# HVPS_SMD-eagle.net
KiCad netlist of a schematic drawn in EAGLE
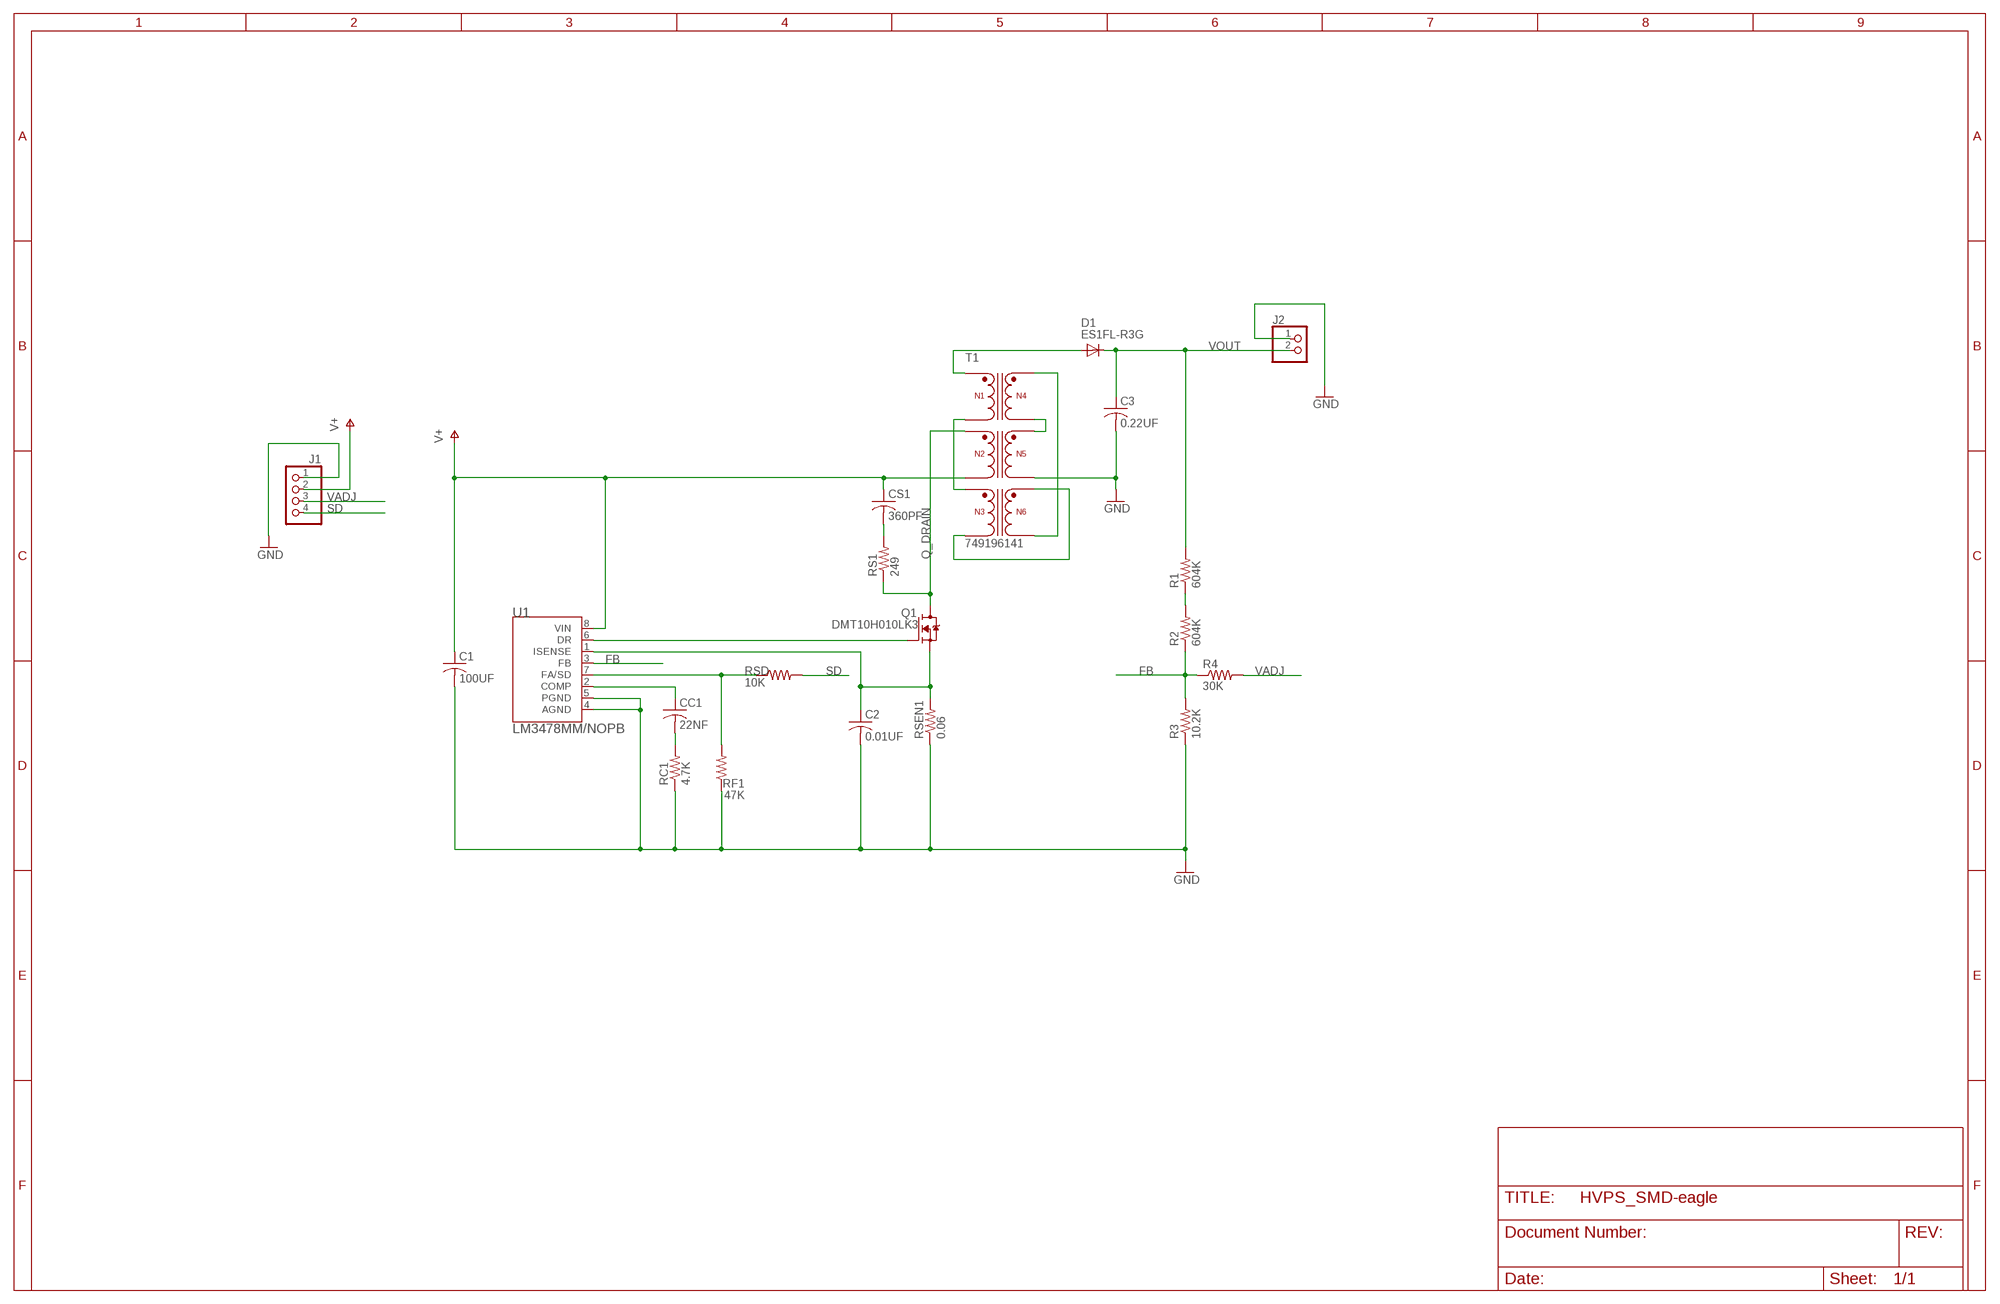
[diagram p0: schematic, sheet 1]

(export (version "E")
  (design (tool "Eeschema 10.0.6"))
  (components
    (comp (ref "C1")
      (value "100UF")
      (footprint "eagle-import:C1210")
      (libsource (lib "eagle-import") (part "C-USC1210"))
    )
    (comp (ref "C2")
      (value "0.01UF")
      (footprint "eagle-import:C0603")
      (libsource (lib "eagle-import") (part "C-USC0603"))
    )
    (comp (ref "C3")
      (value "0.22UF")
      (footprint "eagle-import:C1210")
      (libsource (lib "eagle-import") (part "C-USC1210"))
    )
    (comp (ref "CC1")
      (value "22NF")
      (footprint "eagle-import:C0603")
      (libsource (lib "eagle-import") (part "C-USC0603"))
    )
    (comp (ref "CS1")
      (value "360PF")
      (footprint "eagle-import:C0603")
      (libsource (lib "eagle-import") (part "C-USC0603"))
    )
    (comp (ref "D1")
      (value "ES1FL-R3G")
      (footprint "eagle-import:SMA")
      (libsource (lib "eagle-import") (part "ES1FL-R3G"))
    )
    (comp (ref "J1")
      (value "PINHD-1X4")
      (footprint "eagle-import:1X04")
      (libsource (lib "eagle-import") (part "PINHD-1X4"))
    )
    (comp (ref "J2")
      (value "PINHD-1X2")
      (footprint "eagle-import:1X02")
      (libsource (lib "eagle-import") (part "PINHD-1X2"))
    )
    (comp (ref "Q1")
      (value "DMT10H010LK3")
      (footprint "eagle-import:TO252")
      (libsource (lib "eagle-import") (part "DMT10H010LK3"))
    )
    (comp (ref "R1")
      (value "604K")
      (footprint "eagle-import:R0805")
      (libsource (lib "eagle-import") (part "R-US_R0805"))
    )
    (comp (ref "R2")
      (value "604K")
      (footprint "eagle-import:R0805")
      (libsource (lib "eagle-import") (part "R-US_R0805"))
    )
    (comp (ref "R3")
      (value "10.2K")
      (footprint "eagle-import:R0603")
      (libsource (lib "eagle-import") (part "R-US_R0603"))
    )
    (comp (ref "R4")
      (value "30K")
      (footprint "eagle-import:R0603")
      (libsource (lib "eagle-import") (part "R-US_R0603"))
    )
    (comp (ref "RC1")
      (value "4.7K")
      (footprint "eagle-import:R0805")
      (libsource (lib "eagle-import") (part "R-US_R0805"))
    )
    (comp (ref "RF1")
      (value "47K")
      (footprint "eagle-import:R0603")
      (libsource (lib "eagle-import") (part "R-US_R0603"))
    )
    (comp (ref "RS1")
      (value "249")
      (footprint "eagle-import:R1206")
      (libsource (lib "eagle-import") (part "R-US_R1206"))
    )
    (comp (ref "RSD")
      (value "10K")
      (footprint "eagle-import:R0603")
      (libsource (lib "eagle-import") (part "R-US_R0603"))
    )
    (comp (ref "RSEN1")
      (value "0.06")
      (footprint "eagle-import:R2010")
      (libsource (lib "eagle-import") (part "R-US_R2010"))
    )
    (comp (ref "T1")
      (value "749196141")
      (footprint "eagle-import:749196141")
      (libsource (lib "eagle-import") (part "749196141"))
    )
    (comp (ref "U1")
      (value "LM3478MM/NOPB")
      (footprint "eagle-import:MUA08A")
      (fields (field (name "MANUFACTURER_PART_NUMBER") "LM3478MMNOPB"))
      (libsource (lib "eagle-import") (part "LM3478MM/NOPB"))
    )
  )
  (nets
    (net (code "1") (name "/FB") (class "Default")
      (node (ref "R2") (pin "1") (pinfunction "1_1") (pintype "passive"))
      (node (ref "R3") (pin "2") (pinfunction "2_2") (pintype "passive"))
      (node (ref "R4") (pin "1") (pinfunction "1_1") (pintype "passive"))
      (node (ref "U1") (pin "3") (pinfunction "FB_3") (pintype "passive"))
    )
    (net (code "2") (name "/Q_DRAIN") (class "Default")
      (node (ref "Q1") (pin "3") (pinfunction "D_3") (pintype "passive"))
      (node (ref "RS1") (pin "1") (pinfunction "1_1") (pintype "passive"))
      (node (ref "T1") (pin "2") (pinfunction "N2_2") (pintype "passive"))
    )
    (net (code "3") (name "/SD") (class "Default")
      (node (ref "J1") (pin "4") (pinfunction "4_4") (pintype "passive"))
      (node (ref "RSD") (pin "2") (pinfunction "2_2") (pintype "passive"))
    )
    (net (code "4") (name "/VADJ") (class "Default")
      (node (ref "J1") (pin "3") (pinfunction "3_3") (pintype "passive"))
      (node (ref "R4") (pin "2") (pinfunction "2_2") (pintype "passive"))
    )
    (net (code "5") (name "/VOUT") (class "Default")
      (node (ref "C3") (pin "1") (pinfunction "1_1") (pintype "passive"))
      (node (ref "D1") (pin "C") (pinfunction "C_C") (pintype "passive"))
      (node (ref "J2") (pin "2") (pinfunction "2_2") (pintype "passive"))
      (node (ref "R1") (pin "2") (pinfunction "2_2") (pintype "passive"))
    )
    (net (code "6") (name "GND") (class "Default")
      (node (ref "C1") (pin "2") (pinfunction "2_2") (pintype "passive"))
      (node (ref "C2") (pin "2") (pinfunction "2_2") (pintype "passive"))
      (node (ref "C3") (pin "2") (pinfunction "2_2") (pintype "passive"))
      (node (ref "J1") (pin "1") (pinfunction "1_1") (pintype "passive"))
      (node (ref "J2") (pin "1") (pinfunction "1_1") (pintype "passive"))
      (node (ref "R3") (pin "1") (pinfunction "1_1") (pintype "passive"))
      (node (ref "RC1") (pin "1") (pinfunction "1_1") (pintype "passive"))
      (node (ref "RF1") (pin "1") (pinfunction "1_1") (pintype "passive"))
      (node (ref "RSEN1") (pin "1") (pinfunction "1_1") (pintype "passive"))
      (node (ref "T1") (pin "8") (pinfunction "N5_8") (pintype "passive"))
      (node (ref "U1") (pin "4") (pinfunction "AGND_4") (pintype "passive"))
      (node (ref "U1") (pin "5") (pinfunction "PGND_5") (pintype "passive"))
    )
    (net (code "7") (name "Net-(CC1-Pad2)") (class "Default")
      (node (ref "CC1") (pin "2") (pinfunction "2_2") (pintype "passive"))
      (node (ref "RC1") (pin "2") (pinfunction "2_2") (pintype "passive"))
    )
    (net (code "8") (name "Net-(CS1-Pad2)") (class "Default")
      (node (ref "CS1") (pin "2") (pinfunction "2_2") (pintype "passive"))
      (node (ref "RS1") (pin "2") (pinfunction "2_2") (pintype "passive"))
    )
    (net (code "9") (name "Net-(D1-PadA)") (class "Default")
      (node (ref "D1") (pin "A") (pinfunction "A_A") (pintype "passive"))
      (node (ref "T1") (pin "1") (pinfunction "N1_1") (pintype "passive"))
    )
    (net (code "10") (name "Net-(Q1-G)") (class "Default")
      (node (ref "Q1") (pin "1") (pinfunction "G_1") (pintype "passive"))
      (node (ref "U1") (pin "6") (pinfunction "DR_6") (pintype "power_in"))
    )
    (net (code "11") (name "Net-(Q1-S)") (class "Default")
      (node (ref "C2") (pin "1") (pinfunction "1_1") (pintype "passive"))
      (node (ref "Q1") (pin "2") (pinfunction "S_2") (pintype "passive"))
      (node (ref "RSEN1") (pin "2") (pinfunction "2_2") (pintype "passive"))
      (node (ref "U1") (pin "1") (pinfunction "ISENSE_1") (pintype "passive"))
    )
    (net (code "12") (name "Net-(R1-Pad1)") (class "Default")
      (node (ref "R1") (pin "1") (pinfunction "1_1") (pintype "passive"))
      (node (ref "R2") (pin "2") (pinfunction "2_2") (pintype "passive"))
    )
    (net (code "13") (name "Net-(T1-N1-Pad4)") (class "Default")
      (node (ref "T1") (pin "3") (pinfunction "N3_3") (pintype "passive"))
      (node (ref "T1") (pin "4") (pinfunction "N1_4") (pintype "passive"))
    )
    (net (code "14") (name "Net-(T1-N3-Pad6)") (class "Default")
      (node (ref "T1") (pin "12") (pinfunction "N6_12") (pintype "passive"))
      (node (ref "T1") (pin "6") (pinfunction "N3_6") (pintype "passive"))
    )
    (net (code "15") (name "Net-(T1-N4-Pad7)") (class "Default")
      (node (ref "T1") (pin "11") (pinfunction "N5_11") (pintype "passive"))
      (node (ref "T1") (pin "7") (pinfunction "N4_7") (pintype "passive"))
    )
    (net (code "16") (name "Net-(T1-N4-Pad10)") (class "Default")
      (node (ref "T1") (pin "10") (pinfunction "N4_10") (pintype "passive"))
      (node (ref "T1") (pin "9") (pinfunction "N6_9") (pintype "passive"))
    )
    (net (code "17") (name "Net-(U1-COMP)") (class "Default")
      (node (ref "CC1") (pin "1") (pinfunction "1_1") (pintype "passive"))
      (node (ref "U1") (pin "2") (pinfunction "COMP_2") (pintype "passive"))
    )
    (net (code "18") (name "Net-(U1-FA{slash}SD)") (class "Default")
      (node (ref "RF1") (pin "2") (pinfunction "2_2") (pintype "passive"))
      (node (ref "RSD") (pin "1") (pinfunction "1_1") (pintype "passive"))
      (node (ref "U1") (pin "7") (pinfunction "FA/SD_7") (pintype "passive"))
    )
    (net (code "19") (name "V+") (class "Default")
      (node (ref "C1") (pin "1") (pinfunction "1_1") (pintype "passive"))
      (node (ref "CS1") (pin "1") (pinfunction "1_1") (pintype "passive"))
      (node (ref "J1") (pin "2") (pinfunction "2_2") (pintype "passive"))
      (node (ref "T1") (pin "5") (pinfunction "N2_5") (pintype "passive"))
      (node (ref "U1") (pin "8") (pinfunction "VIN_8") (pintype "input"))
    )
  )
)
